# ADS1299_4_Feather.net
KiCad netlist of a schematic drawn in EAGLE
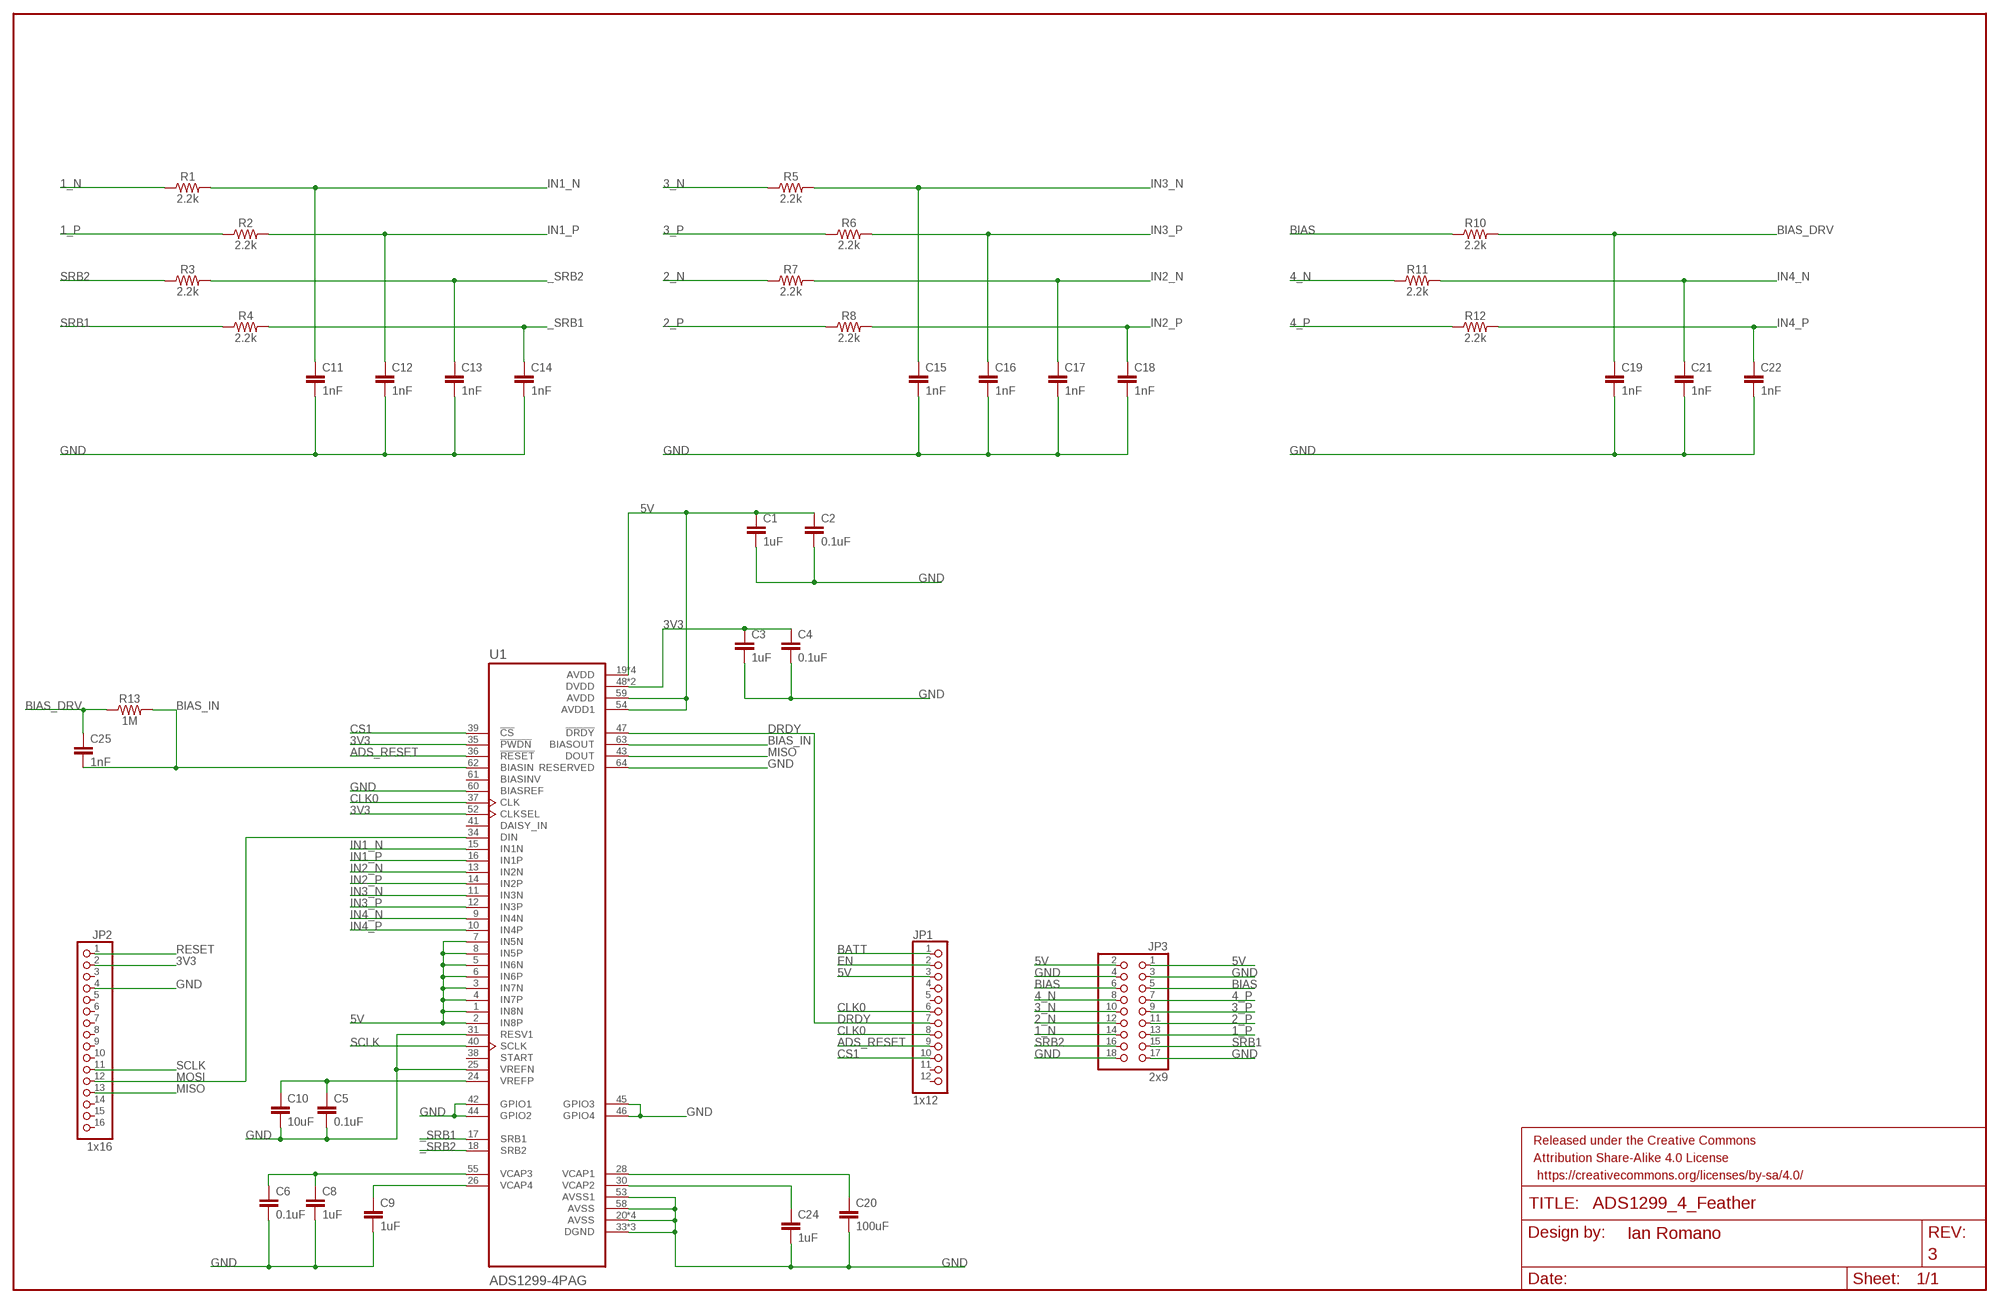
[diagram p0: schematic, sheet 1]

(export (version "E")
  (design (tool "Eeschema 10.0.6"))
  (components
    (comp (ref "C1")
      (value "1uF")
      (footprint "eagle-import:0805")
      (libsource (lib "eagle-import") (part "10UF-0805-10V-10%"))
    )
    (comp (ref "C2")
      (value "0.1uF")
      (footprint "eagle-import:0805")
      (libsource (lib "eagle-import") (part "10UF-0805-10V-10%"))
    )
    (comp (ref "C3")
      (value "1uF")
      (footprint "eagle-import:0805")
      (libsource (lib "eagle-import") (part "10UF-0805-10V-10%"))
    )
    (comp (ref "C4")
      (value "0.1uF")
      (footprint "eagle-import:0805")
      (libsource (lib "eagle-import") (part "10UF-0805-10V-10%"))
    )
    (comp (ref "C5")
      (value "0.1uF")
      (footprint "eagle-import:0805")
      (libsource (lib "eagle-import") (part "10UF-0805-10V-10%"))
    )
    (comp (ref "C6")
      (value "0.1uF")
      (footprint "eagle-import:0805")
      (libsource (lib "eagle-import") (part "10UF-0805-10V-10%"))
    )
    (comp (ref "C8")
      (value "1uF")
      (footprint "eagle-import:0805")
      (libsource (lib "eagle-import") (part "10UF-0805-10V-10%"))
    )
    (comp (ref "C9")
      (value "1uF")
      (footprint "eagle-import:0805")
      (libsource (lib "eagle-import") (part "10UF-0805-10V-10%"))
    )
    (comp (ref "C10")
      (value "10uF")
      (footprint "eagle-import:0805")
      (libsource (lib "eagle-import") (part "10UF-0805-10V-10%"))
    )
    (comp (ref "C11")
      (value "1nF")
      (footprint "eagle-import:0805")
      (libsource (lib "eagle-import") (part "10UF-0805-10V-10%"))
    )
    (comp (ref "C12")
      (value "1nF")
      (footprint "eagle-import:0805")
      (libsource (lib "eagle-import") (part "10UF-0805-10V-10%"))
    )
    (comp (ref "C13")
      (value "1nF")
      (footprint "eagle-import:0805")
      (libsource (lib "eagle-import") (part "10UF-0805-10V-10%"))
    )
    (comp (ref "C14")
      (value "1nF")
      (footprint "eagle-import:0805")
      (libsource (lib "eagle-import") (part "10UF-0805-10V-10%"))
    )
    (comp (ref "C15")
      (value "1nF")
      (footprint "eagle-import:0805")
      (libsource (lib "eagle-import") (part "10UF-0805-10V-10%"))
    )
    (comp (ref "C16")
      (value "1nF")
      (footprint "eagle-import:0805")
      (libsource (lib "eagle-import") (part "10UF-0805-10V-10%"))
    )
    (comp (ref "C17")
      (value "1nF")
      (footprint "eagle-import:0805")
      (libsource (lib "eagle-import") (part "10UF-0805-10V-10%"))
    )
    (comp (ref "C18")
      (value "1nF")
      (footprint "eagle-import:0805")
      (libsource (lib "eagle-import") (part "10UF-0805-10V-10%"))
    )
    (comp (ref "C19")
      (value "1nF")
      (footprint "eagle-import:0805")
      (libsource (lib "eagle-import") (part "10UF-0805-10V-10%"))
    )
    (comp (ref "C20")
      (value "100uF")
      (footprint "eagle-import:0805")
      (libsource (lib "eagle-import") (part "10UF-0805-10V-10%"))
    )
    (comp (ref "C21")
      (value "1nF")
      (footprint "eagle-import:0805")
      (libsource (lib "eagle-import") (part "10UF-0805-10V-10%"))
    )
    (comp (ref "C22")
      (value "1nF")
      (footprint "eagle-import:0805")
      (libsource (lib "eagle-import") (part "10UF-0805-10V-10%"))
    )
    (comp (ref "C24")
      (value "1uF")
      (footprint "eagle-import:0805")
      (libsource (lib "eagle-import") (part "10UF-0805-10V-10%"))
    )
    (comp (ref "C25")
      (value "1nF")
      (footprint "eagle-import:0805")
      (libsource (lib "eagle-import") (part "10UF-0805-10V-10%"))
    )
    (comp (ref "FRAME1")
      (value "FRAME-LEDGER")
      (footprint "eagle-import:CREATIVE_COMMONS")
      (fields (field (name "DESIGNER") "Ian Romano") (field (name "REV") "3"))
      (libsource (lib "eagle-import") (part "FRAME-LEDGER"))
    )
    (comp (ref "JP1")
      (value "1x12")
      (footprint "eagle-import:MICROBUILDER_1X12_ROUND_76MIL")
      (libsource (lib "eagle-import") (part "MICROBUILDER_HEADER-1X1276MIL"))
    )
    (comp (ref "JP2")
      (value "1x16")
      (footprint "eagle-import:MICROBUILDER_1X16_ROUND_76MIL")
      (libsource (lib "eagle-import") (part "MICROBUILDER_HEADER-1X16_76MIL"))
    )
    (comp (ref "JP3")
      (value "2x9")
      (footprint "eagle-import:2X09-BIG")
      (libsource (lib "eagle-import") (part "PINHD-2X9-BIG"))
    )
    (comp (ref "R1")
      (value "2.2k")
      (footprint "eagle-import:0805")
      (libsource (lib "eagle-import") (part "RESISTOR0805"))
    )
    (comp (ref "R2")
      (value "2.2k")
      (footprint "eagle-import:0805")
      (libsource (lib "eagle-import") (part "RESISTOR0805"))
    )
    (comp (ref "R3")
      (value "2.2k")
      (footprint "eagle-import:0805")
      (libsource (lib "eagle-import") (part "RESISTOR0805"))
    )
    (comp (ref "R4")
      (value "2.2k")
      (footprint "eagle-import:0805")
      (libsource (lib "eagle-import") (part "RESISTOR0805"))
    )
    (comp (ref "R5")
      (value "2.2k")
      (footprint "eagle-import:0805")
      (libsource (lib "eagle-import") (part "RESISTOR0805"))
    )
    (comp (ref "R6")
      (value "2.2k")
      (footprint "eagle-import:0805")
      (libsource (lib "eagle-import") (part "RESISTOR0805"))
    )
    (comp (ref "R7")
      (value "2.2k")
      (footprint "eagle-import:0805")
      (libsource (lib "eagle-import") (part "RESISTOR0805"))
    )
    (comp (ref "R8")
      (value "2.2k")
      (footprint "eagle-import:0805")
      (libsource (lib "eagle-import") (part "RESISTOR0805"))
    )
    (comp (ref "R10")
      (value "2.2k")
      (footprint "eagle-import:0805")
      (libsource (lib "eagle-import") (part "RESISTOR0805"))
    )
    (comp (ref "R11")
      (value "2.2k")
      (footprint "eagle-import:0805")
      (libsource (lib "eagle-import") (part "RESISTOR0805"))
    )
    (comp (ref "R12")
      (value "2.2k")
      (footprint "eagle-import:0805")
      (libsource (lib "eagle-import") (part "RESISTOR0805"))
    )
    (comp (ref "R13")
      (value "1M")
      (footprint "eagle-import:0805")
      (libsource (lib "eagle-import") (part "RESISTOR0805"))
    )
    (comp (ref "U1")
      (value "ADS1299-4PAG")
      (footprint "eagle-import:QFP50P1200X1200X120-64N")
      (fields (field (name "MF") "Texas Instruments"))
      (libsource (lib "eagle-import") (part "ADS1299-4PAG"))
    )
  )
  (nets
    (net (code "1") (name "/1_N") (class "Default")
      (node (ref "JP3") (pin "14") (pinfunction "14_14") (pintype "passive"))
      (node (ref "R1") (pin "1") (pinfunction "1_1") (pintype "passive"))
    )
    (net (code "2") (name "/1_P") (class "Default")
      (node (ref "JP3") (pin "13") (pinfunction "13_13") (pintype "passive"))
      (node (ref "R2") (pin "1") (pinfunction "1_1") (pintype "passive"))
    )
    (net (code "3") (name "/2_N") (class "Default")
      (node (ref "JP3") (pin "12") (pinfunction "12_12") (pintype "passive"))
      (node (ref "R7") (pin "1") (pinfunction "1_1") (pintype "passive"))
    )
    (net (code "4") (name "/2_P") (class "Default")
      (node (ref "JP3") (pin "11") (pinfunction "11_11") (pintype "passive"))
      (node (ref "R8") (pin "1") (pinfunction "1_1") (pintype "passive"))
    )
    (net (code "5") (name "/3V3") (class "Default")
      (node (ref "C3") (pin "1") (pinfunction "1_1") (pintype "passive"))
      (node (ref "C4") (pin "1") (pinfunction "1_1") (pintype "passive"))
      (node (ref "JP2") (pin "2") (pinfunction "2_2") (pintype "passive"))
      (node (ref "U1") (pin "35") (pinfunction "~{PWDN}_35") (pintype "input"))
      (node (ref "U1") (pin "48") (pinfunction "DVDD_48") (pintype "power_in"))
      (node (ref "U1") (pin "50") (pinfunction "DVDD_50") (pintype "power_in"))
      (node (ref "U1") (pin "52") (pinfunction "CLKSEL_52") (pintype "input"))
    )
    (net (code "6") (name "/3_N") (class "Default")
      (node (ref "JP3") (pin "10") (pinfunction "10_10") (pintype "passive"))
      (node (ref "R5") (pin "1") (pinfunction "1_1") (pintype "passive"))
    )
    (net (code "7") (name "/3_P") (class "Default")
      (node (ref "JP3") (pin "9") (pinfunction "9_9") (pintype "passive"))
      (node (ref "R6") (pin "1") (pinfunction "1_1") (pintype "passive"))
    )
    (net (code "8") (name "/4_N") (class "Default")
      (node (ref "JP3") (pin "8") (pinfunction "8_8") (pintype "passive"))
      (node (ref "R11") (pin "1") (pinfunction "1_1") (pintype "passive"))
    )
    (net (code "9") (name "/4_P") (class "Default")
      (node (ref "JP3") (pin "7") (pinfunction "7_7") (pintype "passive"))
      (node (ref "R12") (pin "1") (pinfunction "1_1") (pintype "passive"))
    )
    (net (code "10") (name "/5V") (class "Default")
      (node (ref "C1") (pin "1") (pinfunction "1_1") (pintype "passive"))
      (node (ref "C2") (pin "1") (pinfunction "1_1") (pintype "passive"))
      (node (ref "JP1") (pin "3") (pinfunction "3_3") (pintype "passive"))
      (node (ref "JP3") (pin "1") (pinfunction "1_1") (pintype "passive"))
      (node (ref "JP3") (pin "2") (pinfunction "2_2") (pintype "passive"))
      (node (ref "U1") (pin "1") (pinfunction "IN8N_1") (pintype "input"))
      (node (ref "U1") (pin "19") (pinfunction "AVDD_19") (pintype "power_in"))
      (node (ref "U1") (pin "2") (pinfunction "IN8P_2") (pintype "input"))
      (node (ref "U1") (pin "21") (pinfunction "AVDD_21") (pintype "power_in"))
      (node (ref "U1") (pin "22") (pinfunction "AVDD_22") (pintype "power_in"))
      (node (ref "U1") (pin "3") (pinfunction "IN7N_3") (pintype "input"))
      (node (ref "U1") (pin "4") (pinfunction "IN7P_4") (pintype "input"))
      (node (ref "U1") (pin "5") (pinfunction "IN6N_5") (pintype "input"))
      (node (ref "U1") (pin "54") (pinfunction "AVDD1_54") (pintype "power_in"))
      (node (ref "U1") (pin "56") (pinfunction "AVDD_56") (pintype "power_in"))
      (node (ref "U1") (pin "59") (pinfunction "AVDD_59") (pintype "power_in"))
      (node (ref "U1") (pin "6") (pinfunction "IN6P_6") (pintype "input"))
      (node (ref "U1") (pin "7") (pinfunction "IN5N_7") (pintype "input"))
      (node (ref "U1") (pin "8") (pinfunction "IN5P_8") (pintype "input"))
    )
    (net (code "11") (name "/ADS_RESET") (class "Default")
      (node (ref "JP1") (pin "9") (pinfunction "9_9") (pintype "passive"))
      (node (ref "U1") (pin "36") (pinfunction "~{RESET}_36") (pintype "input"))
    )
    (net (code "12") (name "/BATT") (class "Default")
      (node (ref "JP1") (pin "1") (pinfunction "1_1") (pintype "passive"))
    )
    (net (code "13") (name "/BIAS") (class "Default")
      (node (ref "JP3") (pin "5") (pinfunction "5_5") (pintype "passive"))
      (node (ref "JP3") (pin "6") (pinfunction "6_6") (pintype "passive"))
      (node (ref "R10") (pin "1") (pinfunction "1_1") (pintype "passive"))
    )
    (net (code "14") (name "/BIAS_DRV") (class "Default")
      (node (ref "C19") (pin "1") (pinfunction "1_1") (pintype "passive"))
      (node (ref "C25") (pin "1") (pinfunction "1_1") (pintype "passive"))
      (node (ref "R10") (pin "2") (pinfunction "2_2") (pintype "passive"))
      (node (ref "R13") (pin "1") (pinfunction "1_1") (pintype "passive"))
    )
    (net (code "15") (name "/BIAS_IN") (class "Default")
      (node (ref "C25") (pin "2") (pinfunction "2_2") (pintype "passive"))
      (node (ref "R13") (pin "2") (pinfunction "2_2") (pintype "passive"))
      (node (ref "U1") (pin "62") (pinfunction "BIASIN_62") (pintype "input"))
      (node (ref "U1") (pin "63") (pinfunction "BIASOUT_63") (pintype "output"))
    )
    (net (code "16") (name "/CLK0") (class "Default")
      (node (ref "JP1") (pin "6") (pinfunction "6_6") (pintype "passive"))
      (node (ref "JP1") (pin "8") (pinfunction "8_8") (pintype "passive"))
      (node (ref "U1") (pin "37") (pinfunction "CLK_37") (pintype "input"))
    )
    (net (code "17") (name "/CS1") (class "Default")
      (node (ref "JP1") (pin "10") (pinfunction "10_10") (pintype "passive"))
      (node (ref "U1") (pin "39") (pinfunction "~{CS}_39") (pintype "input"))
    )
    (net (code "18") (name "/DRDY") (class "Default")
      (node (ref "JP1") (pin "7") (pinfunction "7_7") (pintype "passive"))
      (node (ref "U1") (pin "47") (pinfunction "~{DRDY}_47") (pintype "output"))
    )
    (net (code "19") (name "/EN") (class "Default")
      (node (ref "JP1") (pin "2") (pinfunction "2_2") (pintype "passive"))
    )
    (net (code "20") (name "/GND") (class "Default")
      (node (ref "C1") (pin "2") (pinfunction "2_2") (pintype "passive"))
      (node (ref "C10") (pin "2") (pinfunction "2_2") (pintype "passive"))
      (node (ref "C11") (pin "2") (pinfunction "2_2") (pintype "passive"))
      (node (ref "C12") (pin "2") (pinfunction "2_2") (pintype "passive"))
      (node (ref "C13") (pin "2") (pinfunction "2_2") (pintype "passive"))
      (node (ref "C14") (pin "2") (pinfunction "2_2") (pintype "passive"))
      (node (ref "C15") (pin "2") (pinfunction "2_2") (pintype "passive"))
      (node (ref "C16") (pin "2") (pinfunction "2_2") (pintype "passive"))
      (node (ref "C17") (pin "2") (pinfunction "2_2") (pintype "passive"))
      (node (ref "C18") (pin "2") (pinfunction "2_2") (pintype "passive"))
      (node (ref "C19") (pin "2") (pinfunction "2_2") (pintype "passive"))
      (node (ref "C2") (pin "2") (pinfunction "2_2") (pintype "passive"))
      (node (ref "C20") (pin "2") (pinfunction "2_2") (pintype "passive"))
      (node (ref "C21") (pin "2") (pinfunction "2_2") (pintype "passive"))
      (node (ref "C22") (pin "2") (pinfunction "2_2") (pintype "passive"))
      (node (ref "C24") (pin "2") (pinfunction "2_2") (pintype "passive"))
      (node (ref "C3") (pin "2") (pinfunction "2_2") (pintype "passive"))
      (node (ref "C4") (pin "2") (pinfunction "2_2") (pintype "passive"))
      (node (ref "C5") (pin "2") (pinfunction "2_2") (pintype "passive"))
      (node (ref "C6") (pin "2") (pinfunction "2_2") (pintype "passive"))
      (node (ref "C8") (pin "2") (pinfunction "2_2") (pintype "passive"))
      (node (ref "C9") (pin "2") (pinfunction "2_2") (pintype "passive"))
      (node (ref "JP2") (pin "4") (pinfunction "4_4") (pintype "passive"))
      (node (ref "JP3") (pin "17") (pinfunction "17_17") (pintype "passive"))
      (node (ref "JP3") (pin "18") (pinfunction "18_18") (pintype "passive"))
      (node (ref "JP3") (pin "3") (pinfunction "3_3") (pintype "passive"))
      (node (ref "JP3") (pin "4") (pinfunction "4_4") (pintype "passive"))
      (node (ref "U1") (pin "20") (pinfunction "AVSS_20") (pintype "power_in"))
      (node (ref "U1") (pin "23") (pinfunction "AVSS_23") (pintype "power_in"))
      (node (ref "U1") (pin "25") (pinfunction "VREFN_25") (pintype "input"))
      (node (ref "U1") (pin "31") (pinfunction "RESV1_31") (pintype "input"))
      (node (ref "U1") (pin "32") (pinfunction "AVSS_32") (pintype "power_in"))
      (node (ref "U1") (pin "33") (pinfunction "DGND_33") (pintype "power_in"))
      (node (ref "U1") (pin "42") (pinfunction "GPIO1_42") (pintype "bidirectional"))
      (node (ref "U1") (pin "44") (pinfunction "GPIO2_44") (pintype "bidirectional"))
      (node (ref "U1") (pin "45") (pinfunction "GPIO3_45") (pintype "bidirectional"))
      (node (ref "U1") (pin "46") (pinfunction "GPIO4_46") (pintype "bidirectional"))
      (node (ref "U1") (pin "49") (pinfunction "DGND_49") (pintype "power_in"))
      (node (ref "U1") (pin "51") (pinfunction "DGND_51") (pintype "power_in"))
      (node (ref "U1") (pin "53") (pinfunction "AVSS1_53") (pintype "power_in"))
      (node (ref "U1") (pin "57") (pinfunction "AVSS_57") (pintype "power_in"))
      (node (ref "U1") (pin "58") (pinfunction "AVSS_58") (pintype "power_in"))
      (node (ref "U1") (pin "60") (pinfunction "BIASREF_60") (pintype "input"))
      (node (ref "U1") (pin "64") (pinfunction "RESERVED_64") (pintype "output"))
    )
    (net (code "21") (name "/IN1_N") (class "Default")
      (node (ref "C11") (pin "1") (pinfunction "1_1") (pintype "passive"))
      (node (ref "R1") (pin "2") (pinfunction "2_2") (pintype "passive"))
      (node (ref "U1") (pin "15") (pinfunction "IN1N_15") (pintype "input"))
    )
    (net (code "22") (name "/IN1_P") (class "Default")
      (node (ref "C12") (pin "1") (pinfunction "1_1") (pintype "passive"))
      (node (ref "R2") (pin "2") (pinfunction "2_2") (pintype "passive"))
      (node (ref "U1") (pin "16") (pinfunction "IN1P_16") (pintype "input"))
    )
    (net (code "23") (name "/IN2_N") (class "Default")
      (node (ref "C17") (pin "1") (pinfunction "1_1") (pintype "passive"))
      (node (ref "R7") (pin "2") (pinfunction "2_2") (pintype "passive"))
      (node (ref "U1") (pin "13") (pinfunction "IN2N_13") (pintype "input"))
    )
    (net (code "24") (name "/IN2_P") (class "Default")
      (node (ref "C18") (pin "1") (pinfunction "1_1") (pintype "passive"))
      (node (ref "R8") (pin "2") (pinfunction "2_2") (pintype "passive"))
      (node (ref "U1") (pin "14") (pinfunction "IN2P_14") (pintype "input"))
    )
    (net (code "25") (name "/IN3_N") (class "Default")
      (node (ref "C15") (pin "1") (pinfunction "1_1") (pintype "passive"))
      (node (ref "R5") (pin "2") (pinfunction "2_2") (pintype "passive"))
      (node (ref "U1") (pin "11") (pinfunction "IN3N_11") (pintype "input"))
    )
    (net (code "26") (name "/IN3_P") (class "Default")
      (node (ref "C16") (pin "1") (pinfunction "1_1") (pintype "passive"))
      (node (ref "R6") (pin "2") (pinfunction "2_2") (pintype "passive"))
      (node (ref "U1") (pin "12") (pinfunction "IN3P_12") (pintype "input"))
    )
    (net (code "27") (name "/IN4_N") (class "Default")
      (node (ref "C21") (pin "1") (pinfunction "1_1") (pintype "passive"))
      (node (ref "R11") (pin "2") (pinfunction "2_2") (pintype "passive"))
      (node (ref "U1") (pin "9") (pinfunction "IN4N_9") (pintype "input"))
    )
    (net (code "28") (name "/IN4_P") (class "Default")
      (node (ref "C22") (pin "1") (pinfunction "1_1") (pintype "passive"))
      (node (ref "R12") (pin "2") (pinfunction "2_2") (pintype "passive"))
      (node (ref "U1") (pin "10") (pinfunction "IN4P_10") (pintype "input"))
    )
    (net (code "29") (name "/MISO") (class "Default")
      (node (ref "JP2") (pin "13") (pinfunction "13_13") (pintype "passive"))
      (node (ref "U1") (pin "43") (pinfunction "DOUT_43") (pintype "output"))
    )
    (net (code "30") (name "/MOSI") (class "Default")
      (node (ref "JP2") (pin "12") (pinfunction "12_12") (pintype "passive"))
      (node (ref "U1") (pin "34") (pinfunction "DIN_34") (pintype "input"))
    )
    (net (code "31") (name "/RESET") (class "Default")
      (node (ref "JP2") (pin "1") (pinfunction "1_1") (pintype "passive"))
    )
    (net (code "32") (name "/SCLK") (class "Default")
      (node (ref "JP2") (pin "11") (pinfunction "11_11") (pintype "passive"))
      (node (ref "U1") (pin "40") (pinfunction "SCLK_40") (pintype "input"))
    )
    (net (code "33") (name "/SRB1") (class "Default")
      (node (ref "JP3") (pin "15") (pinfunction "15_15") (pintype "passive"))
      (node (ref "R4") (pin "1") (pinfunction "1_1") (pintype "passive"))
    )
    (net (code "34") (name "/SRB2") (class "Default")
      (node (ref "JP3") (pin "16") (pinfunction "16_16") (pintype "passive"))
      (node (ref "R3") (pin "1") (pinfunction "1_1") (pintype "passive"))
    )
    (net (code "35") (name "/_SRB1") (class "Default")
      (node (ref "C14") (pin "1") (pinfunction "1_1") (pintype "passive"))
      (node (ref "R4") (pin "2") (pinfunction "2_2") (pintype "passive"))
      (node (ref "U1") (pin "17") (pinfunction "SRB1_17") (pintype "bidirectional"))
    )
    (net (code "36") (name "/_SRB2") (class "Default")
      (node (ref "C13") (pin "1") (pinfunction "1_1") (pintype "passive"))
      (node (ref "R3") (pin "2") (pinfunction "2_2") (pintype "passive"))
      (node (ref "U1") (pin "18") (pinfunction "SRB2_18") (pintype "bidirectional"))
    )
    (net (code "37") (name "Net-(U1-VCAP1)") (class "Default")
      (node (ref "C20") (pin "1") (pinfunction "1_1") (pintype "passive"))
      (node (ref "U1") (pin "28") (pinfunction "VCAP1_28") (pintype "output"))
    )
    (net (code "38") (name "Net-(U1-VCAP2)") (class "Default")
      (node (ref "C24") (pin "1") (pinfunction "1_1") (pintype "passive"))
      (node (ref "U1") (pin "30") (pinfunction "VCAP2_30") (pintype "output"))
    )
    (net (code "39") (name "Net-(U1-VCAP3)") (class "Default")
      (node (ref "C6") (pin "1") (pinfunction "1_1") (pintype "passive"))
      (node (ref "C8") (pin "1") (pinfunction "1_1") (pintype "passive"))
      (node (ref "U1") (pin "55") (pinfunction "VCAP3_55") (pintype "bidirectional"))
    )
    (net (code "40") (name "Net-(U1-VCAP4)") (class "Default")
      (node (ref "C9") (pin "1") (pinfunction "1_1") (pintype "passive"))
      (node (ref "U1") (pin "26") (pinfunction "VCAP4_26") (pintype "bidirectional"))
    )
    (net (code "41") (name "Net-(U1-VREFP)") (class "Default")
      (node (ref "C10") (pin "1") (pinfunction "1_1") (pintype "passive"))
      (node (ref "C5") (pin "1") (pinfunction "1_1") (pintype "passive"))
      (node (ref "U1") (pin "24") (pinfunction "VREFP_24") (pintype "input"))
    )
    (net (code "42") (name "unconnected-(JP1-Pad4)") (class "Default")
      (node (ref "JP1") (pin "4") (pinfunction "4_4") (pintype "passive"))
    )
    (net (code "43") (name "unconnected-(JP1-Pad5)") (class "Default")
      (node (ref "JP1") (pin "5") (pinfunction "5_5") (pintype "passive"))
    )
    (net (code "44") (name "unconnected-(JP1-Pad11)") (class "Default")
      (node (ref "JP1") (pin "11") (pinfunction "11_11") (pintype "passive"))
    )
    (net (code "45") (name "unconnected-(JP1-Pad12)") (class "Default")
      (node (ref "JP1") (pin "12") (pinfunction "12_12") (pintype "passive"))
    )
    (net (code "46") (name "unconnected-(JP2-Pad3)") (class "Default")
      (node (ref "JP2") (pin "3") (pinfunction "3_3") (pintype "passive"))
    )
    (net (code "47") (name "unconnected-(JP2-Pad5)") (class "Default")
      (node (ref "JP2") (pin "5") (pinfunction "5_5") (pintype "passive"))
    )
    (net (code "48") (name "unconnected-(JP2-Pad6)") (class "Default")
      (node (ref "JP2") (pin "6") (pinfunction "6_6") (pintype "passive"))
    )
    (net (code "49") (name "unconnected-(JP2-Pad7)") (class "Default")
      (node (ref "JP2") (pin "7") (pinfunction "7_7") (pintype "passive"))
    )
    (net (code "50") (name "unconnected-(JP2-Pad8)") (class "Default")
      (node (ref "JP2") (pin "8") (pinfunction "8_8") (pintype "passive"))
    )
    (net (code "51") (name "unconnected-(JP2-Pad9)") (class "Default")
      (node (ref "JP2") (pin "9") (pinfunction "9_9") (pintype "passive"))
    )
    (net (code "52") (name "unconnected-(JP2-Pad10)") (class "Default")
      (node (ref "JP2") (pin "10") (pinfunction "10_10") (pintype "passive"))
    )
    (net (code "53") (name "unconnected-(JP2-Pad14)") (class "Default")
      (node (ref "JP2") (pin "14") (pinfunction "14_14") (pintype "passive"))
    )
    (net (code "54") (name "unconnected-(JP2-Pad15)") (class "Default")
      (node (ref "JP2") (pin "15") (pinfunction "15_15") (pintype "passive"))
    )
    (net (code "55") (name "unconnected-(JP2-Pad16)") (class "Default")
      (node (ref "JP2") (pin "16") (pinfunction "16_16") (pintype "passive"))
    )
    (net (code "56") (name "unconnected-(U1-BIASINV-Pad61)") (class "Default")
      (node (ref "U1") (pin "61") (pinfunction "BIASINV_61") (pintype "input"))
    )
    (net (code "57") (name "unconnected-(U1-DAISY_IN-Pad41)") (class "Default")
      (node (ref "U1") (pin "41") (pinfunction "DAISY_IN_41") (pintype "input"))
    )
    (net (code "58") (name "unconnected-(U1-START-Pad38)") (class "Default")
      (node (ref "U1") (pin "38") (pinfunction "START_38") (pintype "input"))
    )
  )
)
